# s2k_kpro.net
KiCad netlist of a schematic drawn in EAGLE
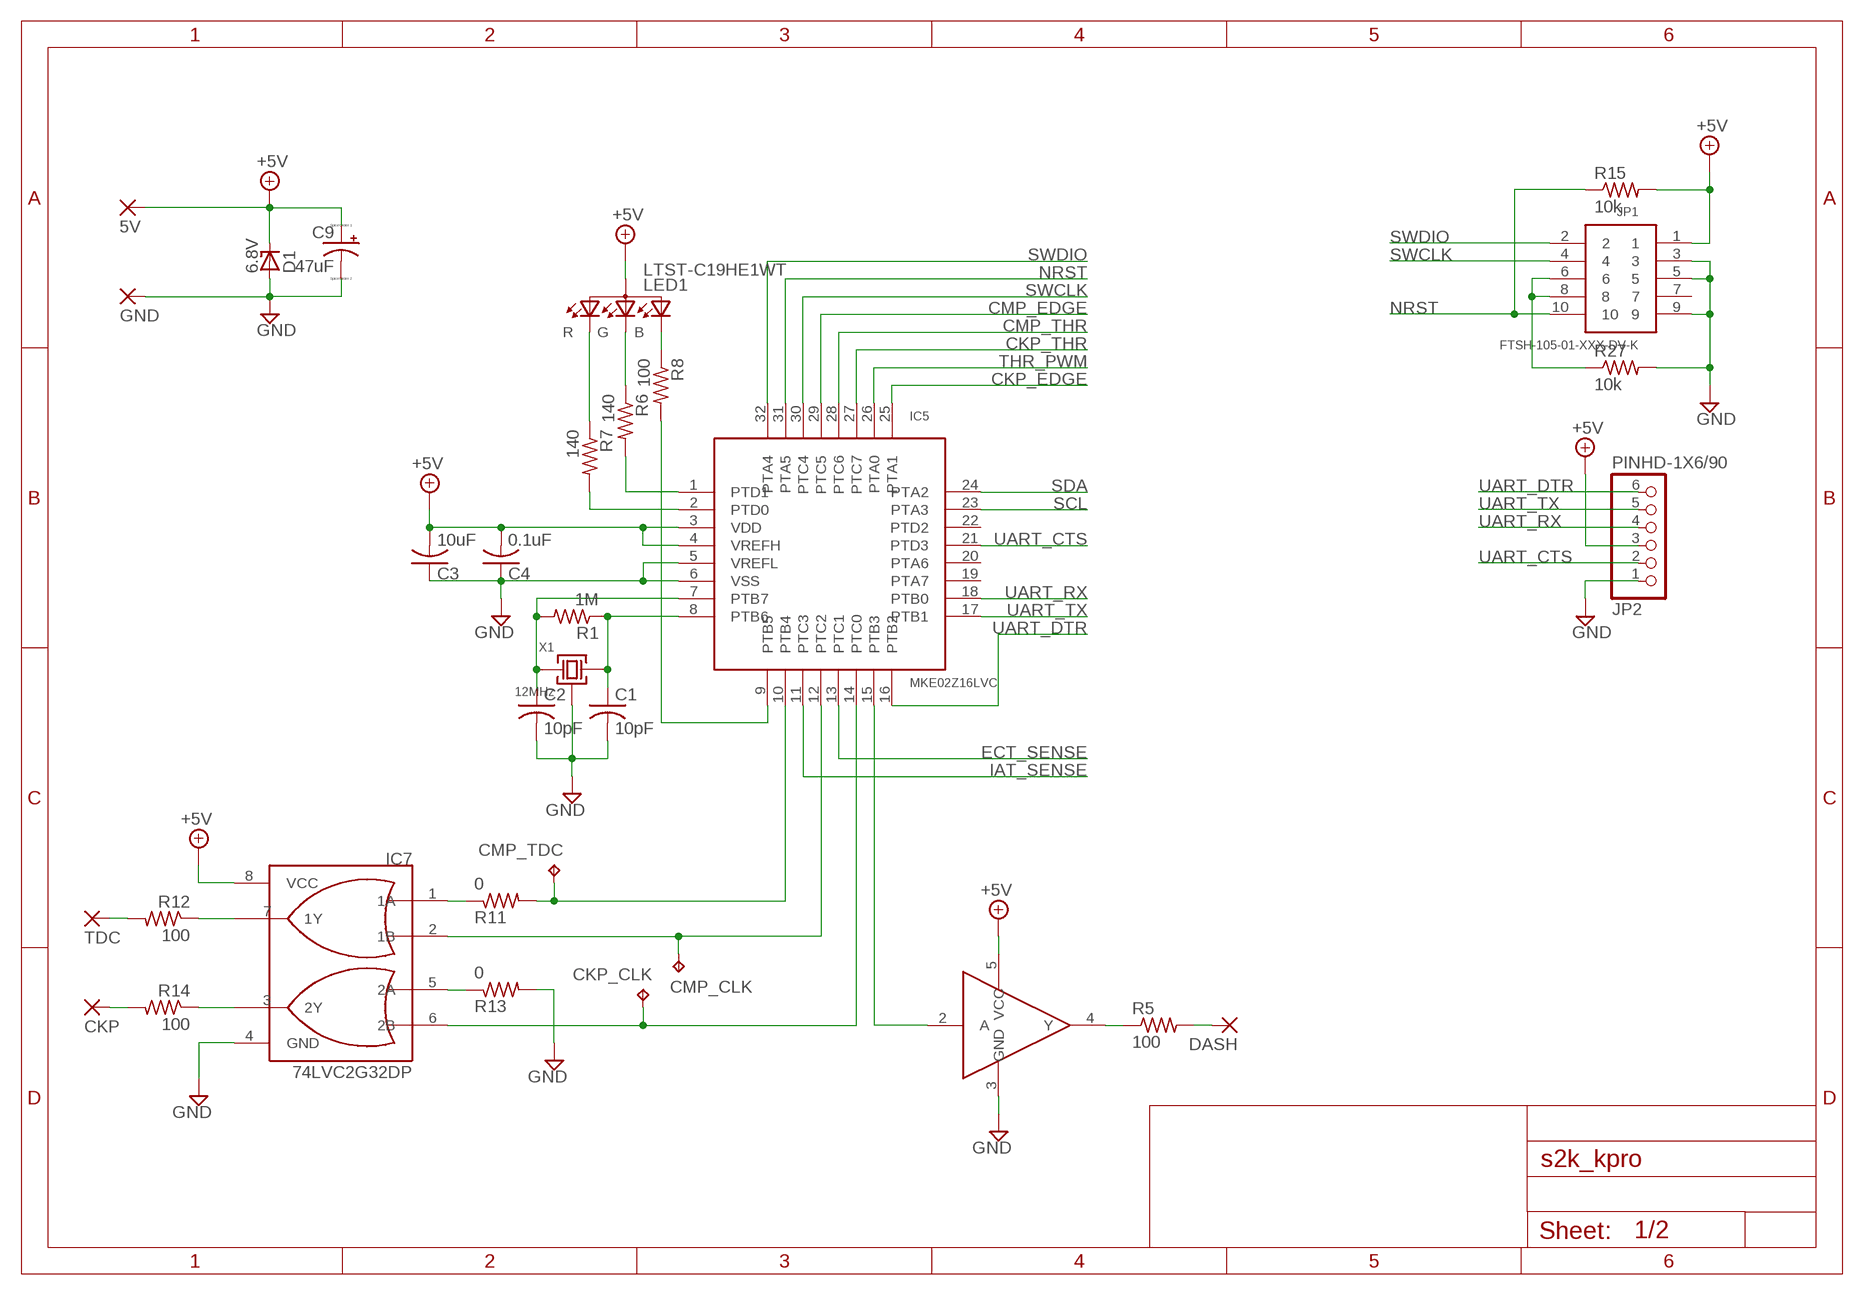
[diagram p0: schematic, sheet 1]
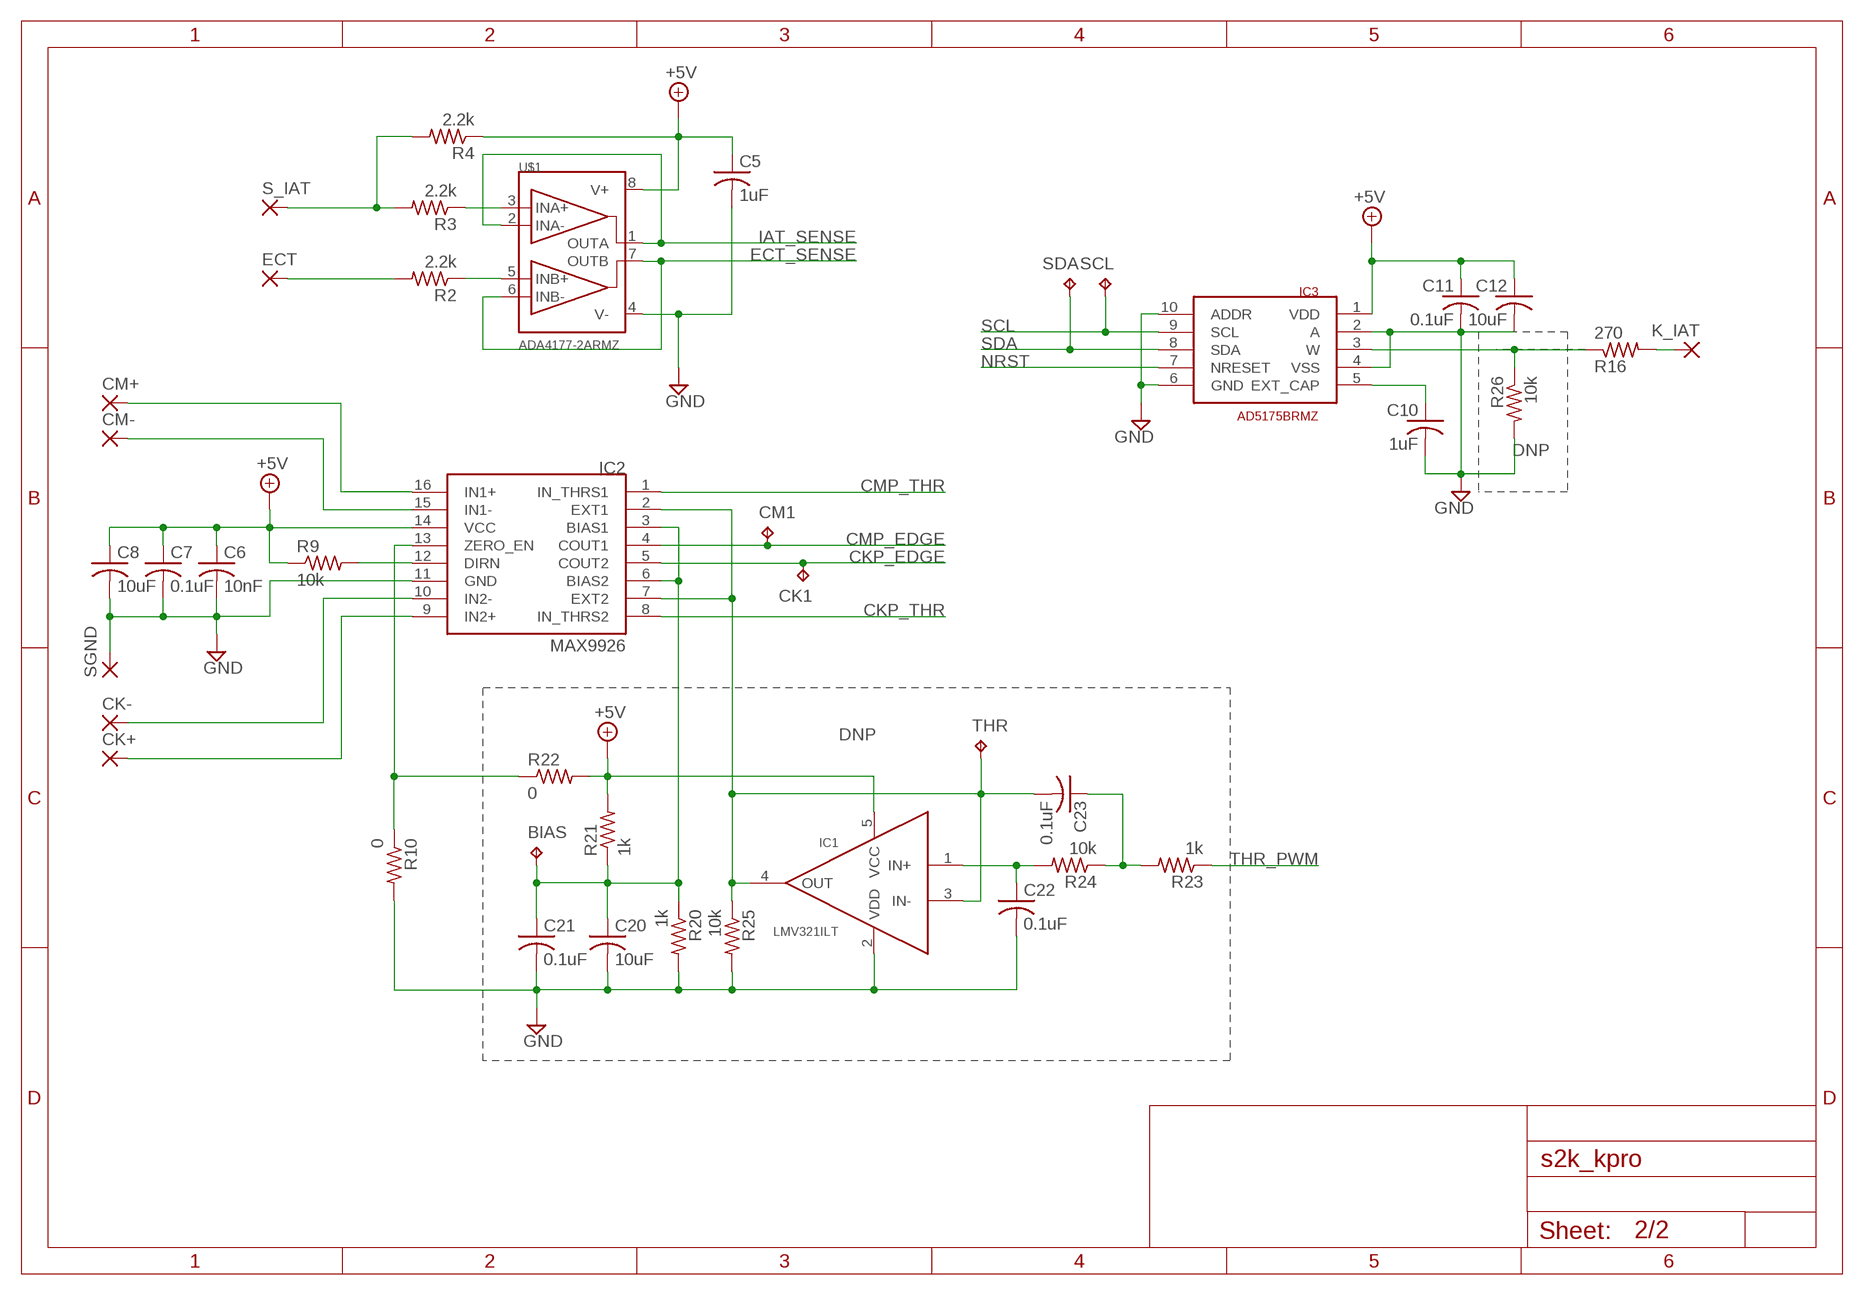
[diagram p1: schematic, sheet 2]

(export (version "E")
  (design (tool "Eeschema 10.0.6"))
  (components
    (comp (ref "5V")
      (value "5V")
      (footprint "eagle-import:P1-20")
      (libsource (lib "eagle-import") (part "SIGPAD-P1-20"))
    )
    (comp (ref "C1")
      (value "10pF")
      (footprint "eagle-import:C0603")
      (libsource (lib "eagle-import") (part "C-USC0603"))
    )
    (comp (ref "C2")
      (value "10pF")
      (footprint "eagle-import:C0603")
      (libsource (lib "eagle-import") (part "C-USC0603"))
    )
    (comp (ref "C3")
      (value "10uF")
      (footprint "eagle-import:C0805")
      (libsource (lib "eagle-import") (part "C-USC0805"))
    )
    (comp (ref "C4")
      (value "0.1uF")
      (footprint "eagle-import:C0603")
      (libsource (lib "eagle-import") (part "C-USC0603"))
    )
    (comp (ref "C9")
      (value "47uF")
      (footprint "eagle-import:D_7343-31R")
      (libsource (lib "eagle-import") (part "CPOL-USD/7343-31R"))
    )
    (comp (ref "CKP")
      (value "SIGPAD-P1-20")
      (footprint "eagle-import:P1-20")
      (libsource (lib "eagle-import") (part "SIGPAD-P1-20"))
    )
    (comp (ref "CKP_CLK")
      (value "TPB2,54")
      (footprint "eagle-import:B2,54")
      (libsource (lib "eagle-import") (part "TPB2,54"))
    )
    (comp (ref "CMP_CLK")
      (value "TPB2,54")
      (footprint "eagle-import:B2,54")
      (libsource (lib "eagle-import") (part "TPB2,54"))
    )
    (comp (ref "CMP_TDC")
      (value "TPB2,54")
      (footprint "eagle-import:B2,54")
      (libsource (lib "eagle-import") (part "TPB2,54"))
    )
    (comp (ref "D1")
      (value "6.8V")
      (footprint "eagle-import:SOT23")
      (libsource (lib "eagle-import") (part "ZENER-DIODESOT23"))
    )
    (comp (ref "DASH")
      (value "SIGPAD-P1-20")
      (footprint "eagle-import:P1-20")
      (libsource (lib "eagle-import") (part "SIGPAD-P1-20"))
    )
    (comp (ref "GND")
      (value "SIGPAD-P1-20")
      (footprint "eagle-import:P1-20")
      (libsource (lib "eagle-import") (part "SIGPAD-P1-20"))
    )
    (comp (ref "IC5")
      (value "MKE02Z16LVC")
      (footprint "eagle-import:LQFP32-7X7")
      (libsource (lib "eagle-import") (part "MKE02Z16LVC"))
    )
    (comp (ref "IC6")
      (value "74LVC1G17SE")
      (footprint "eagle-import:SOT353")
      (libsource (lib "eagle-import") (part "74LVC1G17SE"))
    )
    (comp (ref "IC7")
      (value "74LVC2G32DP")
      (footprint "eagle-import:TSSOP8")
      (libsource (lib "eagle-import") (part "74LVC2G32DP"))
    )
    (comp (ref "JP1")
      (value "FTSH-105-01-XXX-DV-K")
      (footprint "eagle-import:FTSH-105-01-XXX-DV-K")
      (libsource (lib "eagle-import") (part "FTSH-105-01-XXX-DV-K"))
    )
    (comp (ref "JP2")
      (value "PINHD-1X6/90")
      (footprint "eagle-import:1X06_90")
      (libsource (lib "eagle-import") (part "PINHD-1X6/90"))
    )
    (comp (ref "LED1")
      (value "LTST-C19HE1WT")
      (footprint "eagle-import:LED-0606")
      (libsource (lib "eagle-import") (part "LTST-C19HE1WT"))
    )
    (comp (ref "R1")
      (value "1M")
      (footprint "eagle-import:R0603")
      (libsource (lib "eagle-import") (part "R-US_R0603"))
    )
    (comp (ref "R5")
      (value "100")
      (footprint "eagle-import:R0603")
      (libsource (lib "eagle-import") (part "R-US_R0603"))
    )
    (comp (ref "R6")
      (value "140")
      (footprint "eagle-import:R0603")
      (libsource (lib "eagle-import") (part "R-US_R0603"))
    )
    (comp (ref "R7")
      (value "140")
      (footprint "eagle-import:R0603")
      (libsource (lib "eagle-import") (part "R-US_R0603"))
    )
    (comp (ref "R8")
      (value "100")
      (footprint "eagle-import:R0603")
      (libsource (lib "eagle-import") (part "R-US_R0603"))
    )
    (comp (ref "R11")
      (value "0")
      (footprint "eagle-import:R0603")
      (libsource (lib "eagle-import") (part "R-US_R0603"))
    )
    (comp (ref "R12")
      (value "100")
      (footprint "eagle-import:R0603")
      (libsource (lib "eagle-import") (part "R-US_R0603"))
    )
    (comp (ref "R13")
      (value "0")
      (footprint "eagle-import:R0603")
      (libsource (lib "eagle-import") (part "R-US_R0603"))
    )
    (comp (ref "R14")
      (value "100")
      (footprint "eagle-import:R0603")
      (libsource (lib "eagle-import") (part "R-US_R0603"))
    )
    (comp (ref "R15")
      (value "10k")
      (footprint "eagle-import:R0603")
      (libsource (lib "eagle-import") (part "R-US_R0603"))
    )
    (comp (ref "R27")
      (value "10k")
      (footprint "eagle-import:R0603")
      (libsource (lib "eagle-import") (part "R-US_R0603"))
    )
    (comp (ref "TDC")
      (value "SIGPAD-P1-20")
      (footprint "eagle-import:P1-20")
      (libsource (lib "eagle-import") (part "SIGPAD-P1-20"))
    )
    (comp (ref "X1")
      (value "12MHz")
      (footprint "eagle-import:SMD4-2520")
      (libsource (lib "eagle-import") (part "CX2520DB"))
    )
    (comp (ref "BIAS")
      (value "TPB2,54")
      (footprint "eagle-import:B2,54")
      (libsource (lib "eagle-import") (part "TPB2,54"))
    )
    (comp (ref "C5")
      (value "1uF")
      (footprint "eagle-import:C0603")
      (libsource (lib "eagle-import") (part "C-USC0603"))
    )
    (comp (ref "C6")
      (value "10nF")
      (footprint "eagle-import:C0306")
      (libsource (lib "eagle-import") (part "CAP-0306"))
    )
    (comp (ref "C7")
      (value "0.1uF")
      (footprint "eagle-import:C0603")
      (libsource (lib "eagle-import") (part "C-USC0603"))
    )
    (comp (ref "C8")
      (value "10uF")
      (footprint "eagle-import:C0805")
      (libsource (lib "eagle-import") (part "C-USC0805"))
    )
    (comp (ref "C10")
      (value "1uF")
      (footprint "eagle-import:C0603")
      (libsource (lib "eagle-import") (part "C-USC0603"))
    )
    (comp (ref "C11")
      (value "0.1uF")
      (footprint "eagle-import:C0603")
      (libsource (lib "eagle-import") (part "C-USC0603"))
    )
    (comp (ref "C12")
      (value "10uF")
      (footprint "eagle-import:C0805")
      (libsource (lib "eagle-import") (part "C-USC0805"))
    )
    (comp (ref "C20")
      (value "10uF")
      (footprint "eagle-import:C0603")
      (libsource (lib "eagle-import") (part "C-USC0603"))
    )
    (comp (ref "C21")
      (value "0.1uF")
      (footprint "eagle-import:C0603")
      (libsource (lib "eagle-import") (part "C-USC0603"))
    )
    (comp (ref "C22")
      (value "0.1uF")
      (footprint "eagle-import:C0603")
      (libsource (lib "eagle-import") (part "C-USC0603"))
    )
    (comp (ref "C23")
      (value "0.1uF")
      (footprint "eagle-import:C0603")
      (libsource (lib "eagle-import") (part "C-USC0603"))
    )
    (comp (ref "CK+")
      (value "SIGPAD-P1-20")
      (footprint "eagle-import:P1-20")
      (libsource (lib "eagle-import") (part "SIGPAD-P1-20"))
    )
    (comp (ref "CK-")
      (value "SIGPAD-P1-20")
      (footprint "eagle-import:P1-20")
      (libsource (lib "eagle-import") (part "SIGPAD-P1-20"))
    )
    (comp (ref "CK1")
      (value "TPB2,54")
      (footprint "eagle-import:B2,54")
      (libsource (lib "eagle-import") (part "TPB2,54"))
    )
    (comp (ref "CM+")
      (value "SIGPAD-P1-20")
      (footprint "eagle-import:P1-20")
      (libsource (lib "eagle-import") (part "SIGPAD-P1-20"))
    )
    (comp (ref "CM-")
      (value "SIGPAD-P1-20")
      (footprint "eagle-import:P1-20")
      (libsource (lib "eagle-import") (part "SIGPAD-P1-20"))
    )
    (comp (ref "CM1")
      (value "TPB2,54")
      (footprint "eagle-import:B2,54")
      (libsource (lib "eagle-import") (part "TPB2,54"))
    )
    (comp (ref "ECT")
      (value "SIGPAD-P1-20")
      (footprint "eagle-import:P1-20")
      (libsource (lib "eagle-import") (part "SIGPAD-P1-20"))
    )
    (comp (ref "IC1")
      (value "LMV321ILT")
      (footprint "eagle-import:SOT23-5L")
      (libsource (lib "eagle-import") (part "LMV321ILT"))
    )
    (comp (ref "IC2")
      (value "MAX9926")
      (footprint "eagle-import:16-QSOP")
      (libsource (lib "eagle-import") (part "MAX9926"))
    )
    (comp (ref "IC3")
      (value "AD5175BRMZ")
      (footprint "eagle-import:MSOP10")
      (libsource (lib "eagle-import") (part "AD5175BRMZ"))
    )
    (comp (ref "K_IAT")
      (value "SIGPAD-P1-20")
      (footprint "eagle-import:P1-20")
      (libsource (lib "eagle-import") (part "SIGPAD-P1-20"))
    )
    (comp (ref "R2")
      (value "2.2k")
      (footprint "eagle-import:R0603")
      (libsource (lib "eagle-import") (part "R-US_R0603"))
    )
    (comp (ref "R3")
      (value "2.2k")
      (footprint "eagle-import:R0603")
      (libsource (lib "eagle-import") (part "R-US_R0603"))
    )
    (comp (ref "R4")
      (value "2.2k")
      (footprint "eagle-import:R0603")
      (libsource (lib "eagle-import") (part "R-US_R0603"))
    )
    (comp (ref "R9")
      (value "10k")
      (footprint "eagle-import:R0603")
      (libsource (lib "eagle-import") (part "R-US_R0603"))
    )
    (comp (ref "R10")
      (value "0")
      (footprint "eagle-import:R0603")
      (libsource (lib "eagle-import") (part "R-US_R0603"))
    )
    (comp (ref "R16")
      (value "270")
      (footprint "eagle-import:R0603")
      (libsource (lib "eagle-import") (part "R-US_R0603"))
    )
    (comp (ref "R20")
      (value "1k")
      (footprint "eagle-import:R0603")
      (libsource (lib "eagle-import") (part "R-US_R0603"))
    )
    (comp (ref "R21")
      (value "1k")
      (footprint "eagle-import:R0603")
      (libsource (lib "eagle-import") (part "R-US_R0603"))
    )
    (comp (ref "R22")
      (value "0")
      (footprint "eagle-import:R0603")
      (libsource (lib "eagle-import") (part "R-US_R0603"))
    )
    (comp (ref "R23")
      (value "1k")
      (footprint "eagle-import:R0603")
      (libsource (lib "eagle-import") (part "R-US_R0603"))
    )
    (comp (ref "R24")
      (value "10k")
      (footprint "eagle-import:R0603")
      (libsource (lib "eagle-import") (part "R-US_R0603"))
    )
    (comp (ref "R25")
      (value "10k")
      (footprint "eagle-import:R0603")
      (libsource (lib "eagle-import") (part "R-US_R0603"))
    )
    (comp (ref "R26")
      (value "10k")
      (footprint "eagle-import:R0603")
      (libsource (lib "eagle-import") (part "R-US_R0603"))
    )
    (comp (ref "SCL")
      (value "TPB2,54")
      (footprint "eagle-import:B2,54")
      (libsource (lib "eagle-import") (part "TPB2,54"))
    )
    (comp (ref "SDA")
      (value "TPB2,54")
      (footprint "eagle-import:B2,54")
      (libsource (lib "eagle-import") (part "TPB2,54"))
    )
    (comp (ref "SGND")
      (value "SIGPAD-P1-20")
      (footprint "eagle-import:P1-20")
      (libsource (lib "eagle-import") (part "SIGPAD-P1-20"))
    )
    (comp (ref "S_IAT")
      (value "SIGPAD-P1-20")
      (footprint "eagle-import:P1-20")
      (libsource (lib "eagle-import") (part "SIGPAD-P1-20"))
    )
    (comp (ref "THR")
      (value "TPB2,54")
      (footprint "eagle-import:B2,54")
      (libsource (lib "eagle-import") (part "TPB2,54"))
    )
    (comp (ref "U$1")
      (value "ADA4177-2ARMZ")
      (footprint "eagle-import:MSOP08")
      (libsource (lib "eagle-import") (part "ADA4177-2ARMZ"))
    )
  )
  (nets
    (net (code "1") (name "+5V") (class "Default")
      (node (ref "5V") (pin "TP") (pinfunction "P_TP") (pintype "passive"))
      (node (ref "C11") (pin "1") (pinfunction "1_1") (pintype "passive"))
      (node (ref "C12") (pin "1") (pinfunction "1_1") (pintype "passive"))
      (node (ref "C3") (pin "2") (pinfunction "2_2") (pintype "passive"))
      (node (ref "C4") (pin "2") (pinfunction "2_2") (pintype "passive"))
      (node (ref "C5") (pin "1") (pinfunction "1_1") (pintype "passive"))
      (node (ref "C6") (pin "1") (pinfunction "1_1") (pintype "passive"))
      (node (ref "C7") (pin "1") (pinfunction "1_1") (pintype "passive"))
      (node (ref "C8") (pin "1") (pinfunction "1_1") (pintype "passive"))
      (node (ref "C9") (pin "+") (pinfunction "+_+") (pintype "passive"))
      (node (ref "D1") (pin "3") (pinfunction "C_3") (pintype "passive"))
      (node (ref "IC1") (pin "5") (pinfunction "VCC_5") (pintype "bidirectional"))
      (node (ref "IC2") (pin "14") (pinfunction "VCC_14") (pintype "bidirectional"))
      (node (ref "IC3") (pin "1") (pinfunction "VDD_1") (pintype "bidirectional"))
      (node (ref "IC5") (pin "3") (pinfunction "VDD_3") (pintype "bidirectional"))
      (node (ref "IC5") (pin "4") (pinfunction "VREFH_4") (pintype "bidirectional"))
      (node (ref "IC6") (pin "5") (pinfunction "VCC_5") (pintype "bidirectional"))
      (node (ref "IC7") (pin "8") (pinfunction "VCC_8") (pintype "bidirectional"))
      (node (ref "JP1") (pin "1") (pinfunction "1_1") (pintype "bidirectional"))
      (node (ref "JP2") (pin "3") (pinfunction "3_3") (pintype "passive"))
      (node (ref "LED1") (pin "4") (pinfunction "ANODE_4") (pintype "passive"))
      (node (ref "R15") (pin "2") (pinfunction "2_2") (pintype "passive"))
      (node (ref "R21") (pin "2") (pinfunction "2_2") (pintype "passive"))
      (node (ref "R22") (pin "2") (pinfunction "2_2") (pintype "passive"))
      (node (ref "R4") (pin "1") (pinfunction "1_1") (pintype "passive"))
      (node (ref "R9") (pin "1") (pinfunction "1_1") (pintype "passive"))
      (node (ref "U$1") (pin "8") (pinfunction "V+_8") (pintype "bidirectional"))
    )
    (net (code "2") (name "CKP_EDGE") (class "Default")
      (node (ref "CK1") (pin "TP") (pinfunction "TP_TP") (pintype "input"))
      (node (ref "IC2") (pin "5") (pinfunction "COUT2_5") (pintype "bidirectional"))
      (node (ref "IC5") (pin "25") (pinfunction "PTA1_25") (pintype "bidirectional"))
    )
    (net (code "3") (name "CKP_THR") (class "Default")
      (node (ref "IC2") (pin "8") (pinfunction "IN_THRS2_8") (pintype "bidirectional"))
      (node (ref "IC5") (pin "27") (pinfunction "PTC7_27") (pintype "bidirectional"))
    )
    (net (code "4") (name "CMP_EDGE") (class "Default")
      (node (ref "CM1") (pin "TP") (pinfunction "TP_TP") (pintype "input"))
      (node (ref "IC2") (pin "4") (pinfunction "COUT1_4") (pintype "bidirectional"))
      (node (ref "IC5") (pin "29") (pinfunction "PTC5_29") (pintype "bidirectional"))
    )
    (net (code "5") (name "CMP_THR") (class "Default")
      (node (ref "IC2") (pin "1") (pinfunction "IN_THRS1_1") (pintype "bidirectional"))
      (node (ref "IC5") (pin "28") (pinfunction "PTC6_28") (pintype "bidirectional"))
    )
    (net (code "6") (name "ECT_SENSE") (class "Default")
      (node (ref "IC5") (pin "13") (pinfunction "PTC1_13") (pintype "bidirectional"))
      (node (ref "U$1") (pin "6") (pinfunction "INB-_6") (pintype "bidirectional"))
      (node (ref "U$1") (pin "7") (pinfunction "OUTB_7") (pintype "bidirectional"))
    )
    (net (code "7") (name "GND") (class "Default")
      (node (ref "C1") (pin "2") (pinfunction "2_2") (pintype "passive"))
      (node (ref "C10") (pin "2") (pinfunction "2_2") (pintype "passive"))
      (node (ref "C11") (pin "2") (pinfunction "2_2") (pintype "passive"))
      (node (ref "C12") (pin "2") (pinfunction "2_2") (pintype "passive"))
      (node (ref "C2") (pin "2") (pinfunction "2_2") (pintype "passive"))
      (node (ref "C20") (pin "2") (pinfunction "2_2") (pintype "passive"))
      (node (ref "C21") (pin "2") (pinfunction "2_2") (pintype "passive"))
      (node (ref "C22") (pin "2") (pinfunction "2_2") (pintype "passive"))
      (node (ref "C3") (pin "1") (pinfunction "1_1") (pintype "passive"))
      (node (ref "C4") (pin "1") (pinfunction "1_1") (pintype "passive"))
      (node (ref "C5") (pin "2") (pinfunction "2_2") (pintype "passive"))
      (node (ref "C6") (pin "2") (pinfunction "2_2") (pintype "passive"))
      (node (ref "C7") (pin "2") (pinfunction "2_2") (pintype "passive"))
      (node (ref "C8") (pin "2") (pinfunction "2_2") (pintype "passive"))
      (node (ref "C9") (pin "-") (pinfunction "-_-") (pintype "passive"))
      (node (ref "D1") (pin "1") (pinfunction "A_1") (pintype "passive"))
      (node (ref "GND") (pin "TP") (pinfunction "P_TP") (pintype "passive"))
      (node (ref "IC1") (pin "2") (pinfunction "VDD_2") (pintype "bidirectional"))
      (node (ref "IC2") (pin "11") (pinfunction "GND_11") (pintype "bidirectional"))
      (node (ref "IC3") (pin "10") (pinfunction "ADDR_10") (pintype "bidirectional"))
      (node (ref "IC3") (pin "2") (pinfunction "A_2") (pintype "bidirectional"))
      (node (ref "IC3") (pin "4") (pinfunction "VSS_4") (pintype "bidirectional"))
      (node (ref "IC3") (pin "6") (pinfunction "GND_6") (pintype "bidirectional"))
      (node (ref "IC5") (pin "5") (pinfunction "VREFL_5") (pintype "bidirectional"))
      (node (ref "IC5") (pin "6") (pinfunction "VSS_6") (pintype "bidirectional"))
      (node (ref "IC6") (pin "3") (pinfunction "GND_3") (pintype "bidirectional"))
      (node (ref "IC7") (pin "4") (pinfunction "GND_4") (pintype "bidirectional"))
      (node (ref "JP1") (pin "3") (pinfunction "3_3") (pintype "bidirectional"))
      (node (ref "JP1") (pin "5") (pinfunction "5_5") (pintype "bidirectional"))
      (node (ref "JP1") (pin "9") (pinfunction "9_9") (pintype "bidirectional"))
      (node (ref "JP2") (pin "1") (pinfunction "1_1") (pintype "passive"))
      (node (ref "R10") (pin "2") (pinfunction "2_2") (pintype "passive"))
      (node (ref "R13") (pin "2") (pinfunction "2_2") (pintype "passive"))
      (node (ref "R20") (pin "2") (pinfunction "2_2") (pintype "passive"))
      (node (ref "R25") (pin "2") (pinfunction "2_2") (pintype "passive"))
      (node (ref "R26") (pin "2") (pinfunction "2_2") (pintype "passive"))
      (node (ref "R27") (pin "2") (pinfunction "2_2") (pintype "passive"))
      (node (ref "SGND") (pin "TP") (pinfunction "P_TP") (pintype "passive"))
      (node (ref "U$1") (pin "4") (pinfunction "V-_4") (pintype "bidirectional"))
      (node (ref "X1") (pin "2") (pinfunction "GND_2") (pintype "bidirectional"))
      (node (ref "X1") (pin "4") (pinfunction "GND_4") (pintype "bidirectional"))
    )
    (net (code "8") (name "IAT_SENSE") (class "Default")
      (node (ref "IC5") (pin "11") (pinfunction "PTC3_11") (pintype "bidirectional"))
      (node (ref "U$1") (pin "1") (pinfunction "OUTA_1") (pintype "bidirectional"))
      (node (ref "U$1") (pin "2") (pinfunction "INA-_2") (pintype "bidirectional"))
    )
    (net (code "9") (name "NRST") (class "Default")
      (node (ref "IC3") (pin "7") (pinfunction "NRESET_7") (pintype "bidirectional"))
      (node (ref "IC5") (pin "31") (pinfunction "PTA5_31") (pintype "bidirectional"))
      (node (ref "JP1") (pin "10") (pinfunction "10_10") (pintype "bidirectional"))
      (node (ref "R15") (pin "1") (pinfunction "1_1") (pintype "passive"))
    )
    (net (code "10") (name "Net-(C23-Pad1)") (class "Default")
      (node (ref "C23") (pin "1") (pinfunction "1_1") (pintype "passive"))
      (node (ref "R23") (pin "2") (pinfunction "2_2") (pintype "passive"))
      (node (ref "R24") (pin "1") (pinfunction "1_1") (pintype "passive"))
    )
    (net (code "11") (name "Net-(CK+-P)") (class "Default")
      (node (ref "CK+") (pin "TP") (pinfunction "P_TP") (pintype "passive"))
      (node (ref "IC2") (pin "9") (pinfunction "IN2+_9") (pintype "bidirectional"))
    )
    (net (code "12") (name "Net-(CK--P)") (class "Default")
      (node (ref "CK-") (pin "TP") (pinfunction "P_TP") (pintype "passive"))
      (node (ref "IC2") (pin "10") (pinfunction "IN2-_10") (pintype "bidirectional"))
    )
    (net (code "13") (name "Net-(CKP-P)") (class "Default")
      (node (ref "CKP") (pin "TP") (pinfunction "P_TP") (pintype "passive"))
      (node (ref "R14") (pin "2") (pinfunction "2_2") (pintype "passive"))
    )
    (net (code "14") (name "Net-(CM+-P)") (class "Default")
      (node (ref "CM+") (pin "TP") (pinfunction "P_TP") (pintype "passive"))
      (node (ref "IC2") (pin "16") (pinfunction "IN1+_16") (pintype "bidirectional"))
    )
    (net (code "15") (name "Net-(CM--P)") (class "Default")
      (node (ref "CM-") (pin "TP") (pinfunction "P_TP") (pintype "passive"))
      (node (ref "IC2") (pin "15") (pinfunction "IN1-_15") (pintype "bidirectional"))
    )
    (net (code "16") (name "Net-(DASH-P)") (class "Default")
      (node (ref "DASH") (pin "TP") (pinfunction "P_TP") (pintype "passive"))
      (node (ref "R5") (pin "2") (pinfunction "2_2") (pintype "passive"))
    )
    (net (code "17") (name "Net-(ECT-P)") (class "Default")
      (node (ref "ECT") (pin "TP") (pinfunction "P_TP") (pintype "passive"))
      (node (ref "R2") (pin "2") (pinfunction "2_2") (pintype "passive"))
    )
    (net (code "18") (name "Net-(IC1-IN+)") (class "Default")
      (node (ref "C22") (pin "1") (pinfunction "1_1") (pintype "passive"))
      (node (ref "IC1") (pin "1") (pinfunction "IN+_1") (pintype "bidirectional"))
      (node (ref "R24") (pin "2") (pinfunction "2_2") (pintype "passive"))
    )
    (net (code "19") (name "Net-(IC1-IN-)") (class "Default")
      (node (ref "C23") (pin "2") (pinfunction "2_2") (pintype "passive"))
      (node (ref "IC1") (pin "3") (pinfunction "IN-_3") (pintype "bidirectional"))
      (node (ref "IC1") (pin "4") (pinfunction "OUT_4") (pintype "bidirectional"))
      (node (ref "IC2") (pin "2") (pinfunction "EXT1_2") (pintype "bidirectional"))
      (node (ref "IC2") (pin "7") (pinfunction "EXT2_7") (pintype "bidirectional"))
      (node (ref "R25") (pin "1") (pinfunction "1_1") (pintype "passive"))
      (node (ref "THR") (pin "TP") (pinfunction "TP_TP") (pintype "input"))
    )
    (net (code "20") (name "Net-(IC2-BIAS1)") (class "Default")
      (node (ref "BIAS") (pin "TP") (pinfunction "TP_TP") (pintype "input"))
      (node (ref "C20") (pin "1") (pinfunction "1_1") (pintype "passive"))
      (node (ref "C21") (pin "1") (pinfunction "1_1") (pintype "passive"))
      (node (ref "IC2") (pin "3") (pinfunction "BIAS1_3") (pintype "bidirectional"))
      (node (ref "IC2") (pin "6") (pinfunction "BIAS2_6") (pintype "bidirectional"))
      (node (ref "R20") (pin "1") (pinfunction "1_1") (pintype "passive"))
      (node (ref "R21") (pin "1") (pinfunction "1_1") (pintype "passive"))
    )
    (net (code "21") (name "Net-(IC2-DIRN)") (class "Default")
      (node (ref "IC2") (pin "12") (pinfunction "DIRN_12") (pintype "bidirectional"))
      (node (ref "R9") (pin "2") (pinfunction "2_2") (pintype "passive"))
    )
    (net (code "22") (name "Net-(IC2-ZERO_EN)") (class "Default")
      (node (ref "IC2") (pin "13") (pinfunction "ZERO_EN_13") (pintype "bidirectional"))
      (node (ref "R10") (pin "1") (pinfunction "1_1") (pintype "passive"))
      (node (ref "R22") (pin "1") (pinfunction "1_1") (pintype "passive"))
    )
    (net (code "23") (name "Net-(IC3-EXT_CAP)") (class "Default")
      (node (ref "C10") (pin "1") (pinfunction "1_1") (pintype "passive"))
      (node (ref "IC3") (pin "5") (pinfunction "EXT_CAP_5") (pintype "bidirectional"))
    )
    (net (code "24") (name "Net-(IC3-W)") (class "Default")
      (node (ref "IC3") (pin "3") (pinfunction "W_3") (pintype "bidirectional"))
      (node (ref "R16") (pin "1") (pinfunction "1_1") (pintype "passive"))
      (node (ref "R26") (pin "1") (pinfunction "1_1") (pintype "passive"))
    )
    (net (code "25") (name "Net-(IC5-PTB3)") (class "Default")
      (node (ref "IC5") (pin "15") (pinfunction "PTB3_15") (pintype "bidirectional"))
      (node (ref "IC6") (pin "2") (pinfunction "A_2") (pintype "bidirectional"))
    )
    (net (code "26") (name "Net-(IC5-PTB4)") (class "Default")
      (node (ref "CMP_TDC") (pin "TP") (pinfunction "TP_TP") (pintype "input"))
      (node (ref "IC5") (pin "10") (pinfunction "PTB4_10") (pintype "bidirectional"))
      (node (ref "R11") (pin "2") (pinfunction "2_2") (pintype "passive"))
    )
    (net (code "27") (name "Net-(IC5-PTB5)") (class "Default")
      (node (ref "IC5") (pin "9") (pinfunction "PTB5_9") (pintype "bidirectional"))
      (node (ref "R8") (pin "2") (pinfunction "2_2") (pintype "passive"))
    )
    (net (code "28") (name "Net-(IC5-PTB6)") (class "Default")
      (node (ref "C1") (pin "1") (pinfunction "1_1") (pintype "passive"))
      (node (ref "IC5") (pin "8") (pinfunction "PTB6_8") (pintype "bidirectional"))
      (node (ref "R1") (pin "1") (pinfunction "1_1") (pintype "passive"))
      (node (ref "X1") (pin "1") (pinfunction "1_1") (pintype "bidirectional"))
    )
    (net (code "29") (name "Net-(IC5-PTB7)") (class "Default")
      (node (ref "C2") (pin "1") (pinfunction "1_1") (pintype "passive"))
      (node (ref "IC5") (pin "7") (pinfunction "PTB7_7") (pintype "bidirectional"))
      (node (ref "R1") (pin "2") (pinfunction "2_2") (pintype "passive"))
      (node (ref "X1") (pin "3") (pinfunction "2_3") (pintype "bidirectional"))
    )
    (net (code "30") (name "Net-(IC5-PTC0)") (class "Default")
      (node (ref "CKP_CLK") (pin "TP") (pinfunction "TP_TP") (pintype "input"))
      (node (ref "IC5") (pin "14") (pinfunction "PTC0_14") (pintype "bidirectional"))
      (node (ref "IC7") (pin "6") (pinfunction "2B_6") (pintype "bidirectional"))
    )
    (net (code "31") (name "Net-(IC5-PTC2)") (class "Default")
      (node (ref "CMP_CLK") (pin "TP") (pinfunction "TP_TP") (pintype "input"))
      (node (ref "IC5") (pin "12") (pinfunction "PTC2_12") (pintype "bidirectional"))
      (node (ref "IC7") (pin "2") (pinfunction "1B_2") (pintype "bidirectional"))
    )
    (net (code "32") (name "Net-(IC5-PTD0)") (class "Default")
      (node (ref "IC5") (pin "2") (pinfunction "PTD0_2") (pintype "bidirectional"))
      (node (ref "R7") (pin "2") (pinfunction "2_2") (pintype "passive"))
    )
    (net (code "33") (name "Net-(IC5-PTD1)") (class "Default")
      (node (ref "IC5") (pin "1") (pinfunction "PTD1_1") (pintype "bidirectional"))
      (node (ref "R6") (pin "2") (pinfunction "2_2") (pintype "passive"))
    )
    (net (code "34") (name "Net-(IC6-Y)") (class "Default")
      (node (ref "IC6") (pin "4") (pinfunction "Y_4") (pintype "bidirectional"))
      (node (ref "R5") (pin "1") (pinfunction "1_1") (pintype "passive"))
    )
    (net (code "35") (name "Net-(IC7-1A)") (class "Default")
      (node (ref "IC7") (pin "1") (pinfunction "1A_1") (pintype "bidirectional"))
      (node (ref "R11") (pin "1") (pinfunction "1_1") (pintype "passive"))
    )
    (net (code "36") (name "Net-(IC7-1Y)") (class "Default")
      (node (ref "IC7") (pin "7") (pinfunction "1Y_7") (pintype "bidirectional"))
      (node (ref "R12") (pin "1") (pinfunction "1_1") (pintype "passive"))
    )
    (net (code "37") (name "Net-(IC7-2A)") (class "Default")
      (node (ref "IC7") (pin "5") (pinfunction "2A_5") (pintype "bidirectional"))
      (node (ref "R13") (pin "1") (pinfunction "1_1") (pintype "passive"))
    )
    (net (code "38") (name "Net-(IC7-2Y)") (class "Default")
      (node (ref "IC7") (pin "3") (pinfunction "2Y_3") (pintype "bidirectional"))
      (node (ref "R14") (pin "1") (pinfunction "1_1") (pintype "passive"))
    )
    (net (code "39") (name "Net-(JP1-Pad6)") (class "Default")
      (node (ref "JP1") (pin "6") (pinfunction "6_6") (pintype "bidirectional"))
      (node (ref "JP1") (pin "8") (pinfunction "8_8") (pintype "bidirectional"))
      (node (ref "R27") (pin "1") (pinfunction "1_1") (pintype "passive"))
    )
    (net (code "40") (name "Net-(K_IAT-P)") (class "Default")
      (node (ref "K_IAT") (pin "TP") (pinfunction "P_TP") (pintype "passive"))
      (node (ref "R16") (pin "2") (pinfunction "2_2") (pintype "passive"))
    )
    (net (code "41") (name "Net-(LED1-B)") (class "Default")
      (node (ref "LED1") (pin "3") (pinfunction "B_3") (pintype "passive"))
      (node (ref "R8") (pin "1") (pinfunction "1_1") (pintype "passive"))
    )
    (net (code "42") (name "Net-(LED1-G)") (class "Default")
      (node (ref "LED1") (pin "2") (pinfunction "G_2") (pintype "passive"))
      (node (ref "R6") (pin "1") (pinfunction "1_1") (pintype "passive"))
    )
    (net (code "43") (name "Net-(LED1-R)") (class "Default")
      (node (ref "LED1") (pin "1") (pinfunction "R_1") (pintype "passive"))
      (node (ref "R7") (pin "1") (pinfunction "1_1") (pintype "passive"))
    )
    (net (code "44") (name "Net-(S_IAT-P)") (class "Default")
      (node (ref "R3") (pin "2") (pinfunction "2_2") (pintype "passive"))
      (node (ref "R4") (pin "2") (pinfunction "2_2") (pintype "passive"))
      (node (ref "S_IAT") (pin "TP") (pinfunction "P_TP") (pintype "passive"))
    )
    (net (code "45") (name "Net-(TDC-P)") (class "Default")
      (node (ref "R12") (pin "2") (pinfunction "2_2") (pintype "passive"))
      (node (ref "TDC") (pin "TP") (pinfunction "P_TP") (pintype "passive"))
    )
    (net (code "46") (name "Net-(U$1-INA+)") (class "Default")
      (node (ref "R3") (pin "1") (pinfunction "1_1") (pintype "passive"))
      (node (ref "U$1") (pin "3") (pinfunction "INA+_3") (pintype "bidirectional"))
    )
    (net (code "47") (name "Net-(U$1-INB+)") (class "Default")
      (node (ref "R2") (pin "1") (pinfunction "1_1") (pintype "passive"))
      (node (ref "U$1") (pin "5") (pinfunction "INB+_5") (pintype "bidirectional"))
    )
    (net (code "48") (name "SCL") (class "Default")
      (node (ref "IC3") (pin "9") (pinfunction "SCL_9") (pintype "bidirectional"))
      (node (ref "IC5") (pin "23") (pinfunction "PTA3_23") (pintype "bidirectional"))
      (node (ref "SCL") (pin "TP") (pinfunction "TP_TP") (pintype "input"))
    )
    (net (code "49") (name "SDA") (class "Default")
      (node (ref "IC3") (pin "8") (pinfunction "SDA_8") (pintype "bidirectional"))
      (node (ref "IC5") (pin "24") (pinfunction "PTA2_24") (pintype "bidirectional"))
      (node (ref "SDA") (pin "TP") (pinfunction "TP_TP") (pintype "input"))
    )
    (net (code "50") (name "SWCLK") (class "Default")
      (node (ref "IC5") (pin "30") (pinfunction "PTC4_30") (pintype "bidirectional"))
      (node (ref "JP1") (pin "4") (pinfunction "4_4") (pintype "bidirectional"))
    )
    (net (code "51") (name "SWDIO") (class "Default")
      (node (ref "IC5") (pin "32") (pinfunction "PTA4_32") (pintype "bidirectional"))
      (node (ref "JP1") (pin "2") (pinfunction "2_2") (pintype "bidirectional"))
    )
    (net (code "52") (name "THR_PWM") (class "Default")
      (node (ref "IC5") (pin "26") (pinfunction "PTA0_26") (pintype "bidirectional"))
      (node (ref "R23") (pin "1") (pinfunction "1_1") (pintype "passive"))
    )
    (net (code "53") (name "UART_CTS") (class "Default")
      (node (ref "IC5") (pin "21") (pinfunction "PTD3_21") (pintype "bidirectional"))
      (node (ref "JP2") (pin "2") (pinfunction "2_2") (pintype "passive"))
    )
    (net (code "54") (name "UART_DTR") (class "Default")
      (node (ref "IC5") (pin "16") (pinfunction "PTB2_16") (pintype "bidirectional"))
      (node (ref "JP2") (pin "6") (pinfunction "6_6") (pintype "passive"))
    )
    (net (code "55") (name "UART_RX") (class "Default")
      (node (ref "IC5") (pin "18") (pinfunction "PTB0_18") (pintype "bidirectional"))
      (node (ref "JP2") (pin "4") (pinfunction "4_4") (pintype "passive"))
    )
    (net (code "56") (name "UART_TX") (class "Default")
      (node (ref "IC5") (pin "17") (pinfunction "PTB1_17") (pintype "bidirectional"))
      (node (ref "JP2") (pin "5") (pinfunction "5_5") (pintype "passive"))
    )
    (net (code "57") (name "unconnected-(IC5-PTA6-Pad20)") (class "Default")
      (node (ref "IC5") (pin "20") (pinfunction "PTA6_20") (pintype "bidirectional"))
    )
    (net (code "58") (name "unconnected-(IC5-PTA7-Pad19)") (class "Default")
      (node (ref "IC5") (pin "19") (pinfunction "PTA7_19") (pintype "bidirectional"))
    )
    (net (code "59") (name "unconnected-(IC5-PTD2-Pad22)") (class "Default")
      (node (ref "IC5") (pin "22") (pinfunction "PTD2_22") (pintype "bidirectional"))
    )
    (net (code "60") (name "unconnected-(JP1-Pad7)") (class "Default")
      (node (ref "JP1") (pin "7") (pinfunction "7_7") (pintype "bidirectional"))
    )
  )
)
